# Transceiver_schematic.net
KiCad netlist of a schematic drawn in EAGLE
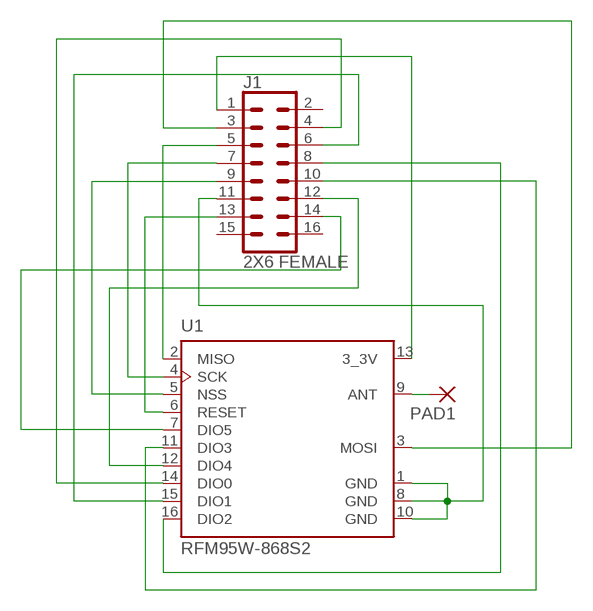
[diagram p0: schematic, sheet 1]

(export (version "E")
  (design (tool "Eeschema 10.0.6"))
  (components
    (comp (ref "J1")
      (value "2X6 FEMALE")
      (footprint "eagle-import:2X7")
      (libsource (lib "eagle-import") (part "SENSOR_BREAKOUTPTH_FEMALE"))
    )
    (comp (ref "PAD1")
      (value "2,54/1,0")
      (footprint "eagle-import:2,54_1,0")
      (libsource (lib "eagle-import") (part "2,54/1,0"))
    )
    (comp (ref "U1")
      (value "RFM95W-868S2")
      (footprint "eagle-import:XCVR_RFM95W-868S2")
      (fields (field (name "MF") "RF"))
      (libsource (lib "eagle-import") (part "RFM95W-868S2"))
    )
  )
  (nets
    (net (code "1") (name "Net-(J1-Pad11)") (class "Default")
      (node (ref "J1") (pin "11") (pinfunction "11_11") (pintype "passive"))
      (node (ref "U1") (pin "1") (pinfunction "GND_1") (pintype "power_in"))
      (node (ref "U1") (pin "10") (pinfunction "GND_10") (pintype "power_in"))
      (node (ref "U1") (pin "8") (pinfunction "GND_8") (pintype "power_in"))
    )
    (net (code "2") (name "Net-(PAD1-P)") (class "Default")
      (node (ref "PAD1") (pin "1") (pinfunction "P_1") (pintype "passive"))
      (node (ref "U1") (pin "9") (pinfunction "ANT_9") (pintype "passive"))
    )
    (net (code "3") (name "Net-(U1-3_3V)") (class "Default")
      (node (ref "J1") (pin "1") (pinfunction "1_1") (pintype "passive"))
      (node (ref "U1") (pin "13") (pinfunction "3_3V_13") (pintype "power_in"))
    )
    (net (code "4") (name "Net-(U1-DIO0)") (class "Default")
      (node (ref "J1") (pin "4") (pinfunction "4_4") (pintype "passive"))
      (node (ref "U1") (pin "14") (pinfunction "DIO0_14") (pintype "bidirectional"))
    )
    (net (code "5") (name "Net-(U1-DIO1)") (class "Default")
      (node (ref "J1") (pin "6") (pinfunction "6_6") (pintype "passive"))
      (node (ref "U1") (pin "15") (pinfunction "DIO1_15") (pintype "bidirectional"))
    )
    (net (code "6") (name "Net-(U1-DIO2)") (class "Default")
      (node (ref "J1") (pin "8") (pinfunction "8_8") (pintype "passive"))
      (node (ref "U1") (pin "16") (pinfunction "DIO2_16") (pintype "bidirectional"))
    )
    (net (code "7") (name "Net-(U1-DIO3)") (class "Default")
      (node (ref "J1") (pin "10") (pinfunction "10_10") (pintype "passive"))
      (node (ref "U1") (pin "11") (pinfunction "DIO3_11") (pintype "bidirectional"))
    )
    (net (code "8") (name "Net-(U1-DIO4)") (class "Default")
      (node (ref "J1") (pin "12") (pinfunction "12_12") (pintype "passive"))
      (node (ref "U1") (pin "12") (pinfunction "DIO4_12") (pintype "bidirectional"))
    )
    (net (code "9") (name "Net-(U1-DIO5)") (class "Default")
      (node (ref "J1") (pin "14") (pinfunction "14_14") (pintype "passive"))
      (node (ref "U1") (pin "7") (pinfunction "DIO5_7") (pintype "bidirectional"))
    )
    (net (code "10") (name "Net-(U1-MISO)") (class "Default")
      (node (ref "J1") (pin "5") (pinfunction "5_5") (pintype "passive"))
      (node (ref "U1") (pin "2") (pinfunction "MISO_2") (pintype "input"))
    )
    (net (code "11") (name "Net-(U1-MOSI)") (class "Default")
      (node (ref "J1") (pin "3") (pinfunction "3_3") (pintype "passive"))
      (node (ref "U1") (pin "3") (pinfunction "MOSI_3") (pintype "output"))
    )
    (net (code "12") (name "Net-(U1-NSS)") (class "Default")
      (node (ref "J1") (pin "9") (pinfunction "9_9") (pintype "passive"))
      (node (ref "U1") (pin "5") (pinfunction "NSS_5") (pintype "input"))
    )
    (net (code "13") (name "Net-(U1-RESET)") (class "Default")
      (node (ref "J1") (pin "13") (pinfunction "13_13") (pintype "passive"))
      (node (ref "U1") (pin "6") (pinfunction "RESET_6") (pintype "bidirectional"))
    )
    (net (code "14") (name "Net-(U1-SCK)") (class "Default")
      (node (ref "J1") (pin "7") (pinfunction "7_7") (pintype "passive"))
      (node (ref "U1") (pin "4") (pinfunction "SCK_4") (pintype "input"))
    )
    (net (code "15") (name "unconnected-(J1-Pad2)") (class "Default")
      (node (ref "J1") (pin "2") (pinfunction "2_2") (pintype "passive"))
    )
    (net (code "16") (name "unconnected-(J1-Pad15)") (class "Default")
      (node (ref "J1") (pin "15") (pinfunction "15_15") (pintype "passive"))
    )
    (net (code "17") (name "unconnected-(J1-Pad16)") (class "Default")
      (node (ref "J1") (pin "16") (pinfunction "16_16") (pintype "passive"))
    )
  )
)
